# STM32.net
KiCad netlist of a schematic drawn in Altium Designer
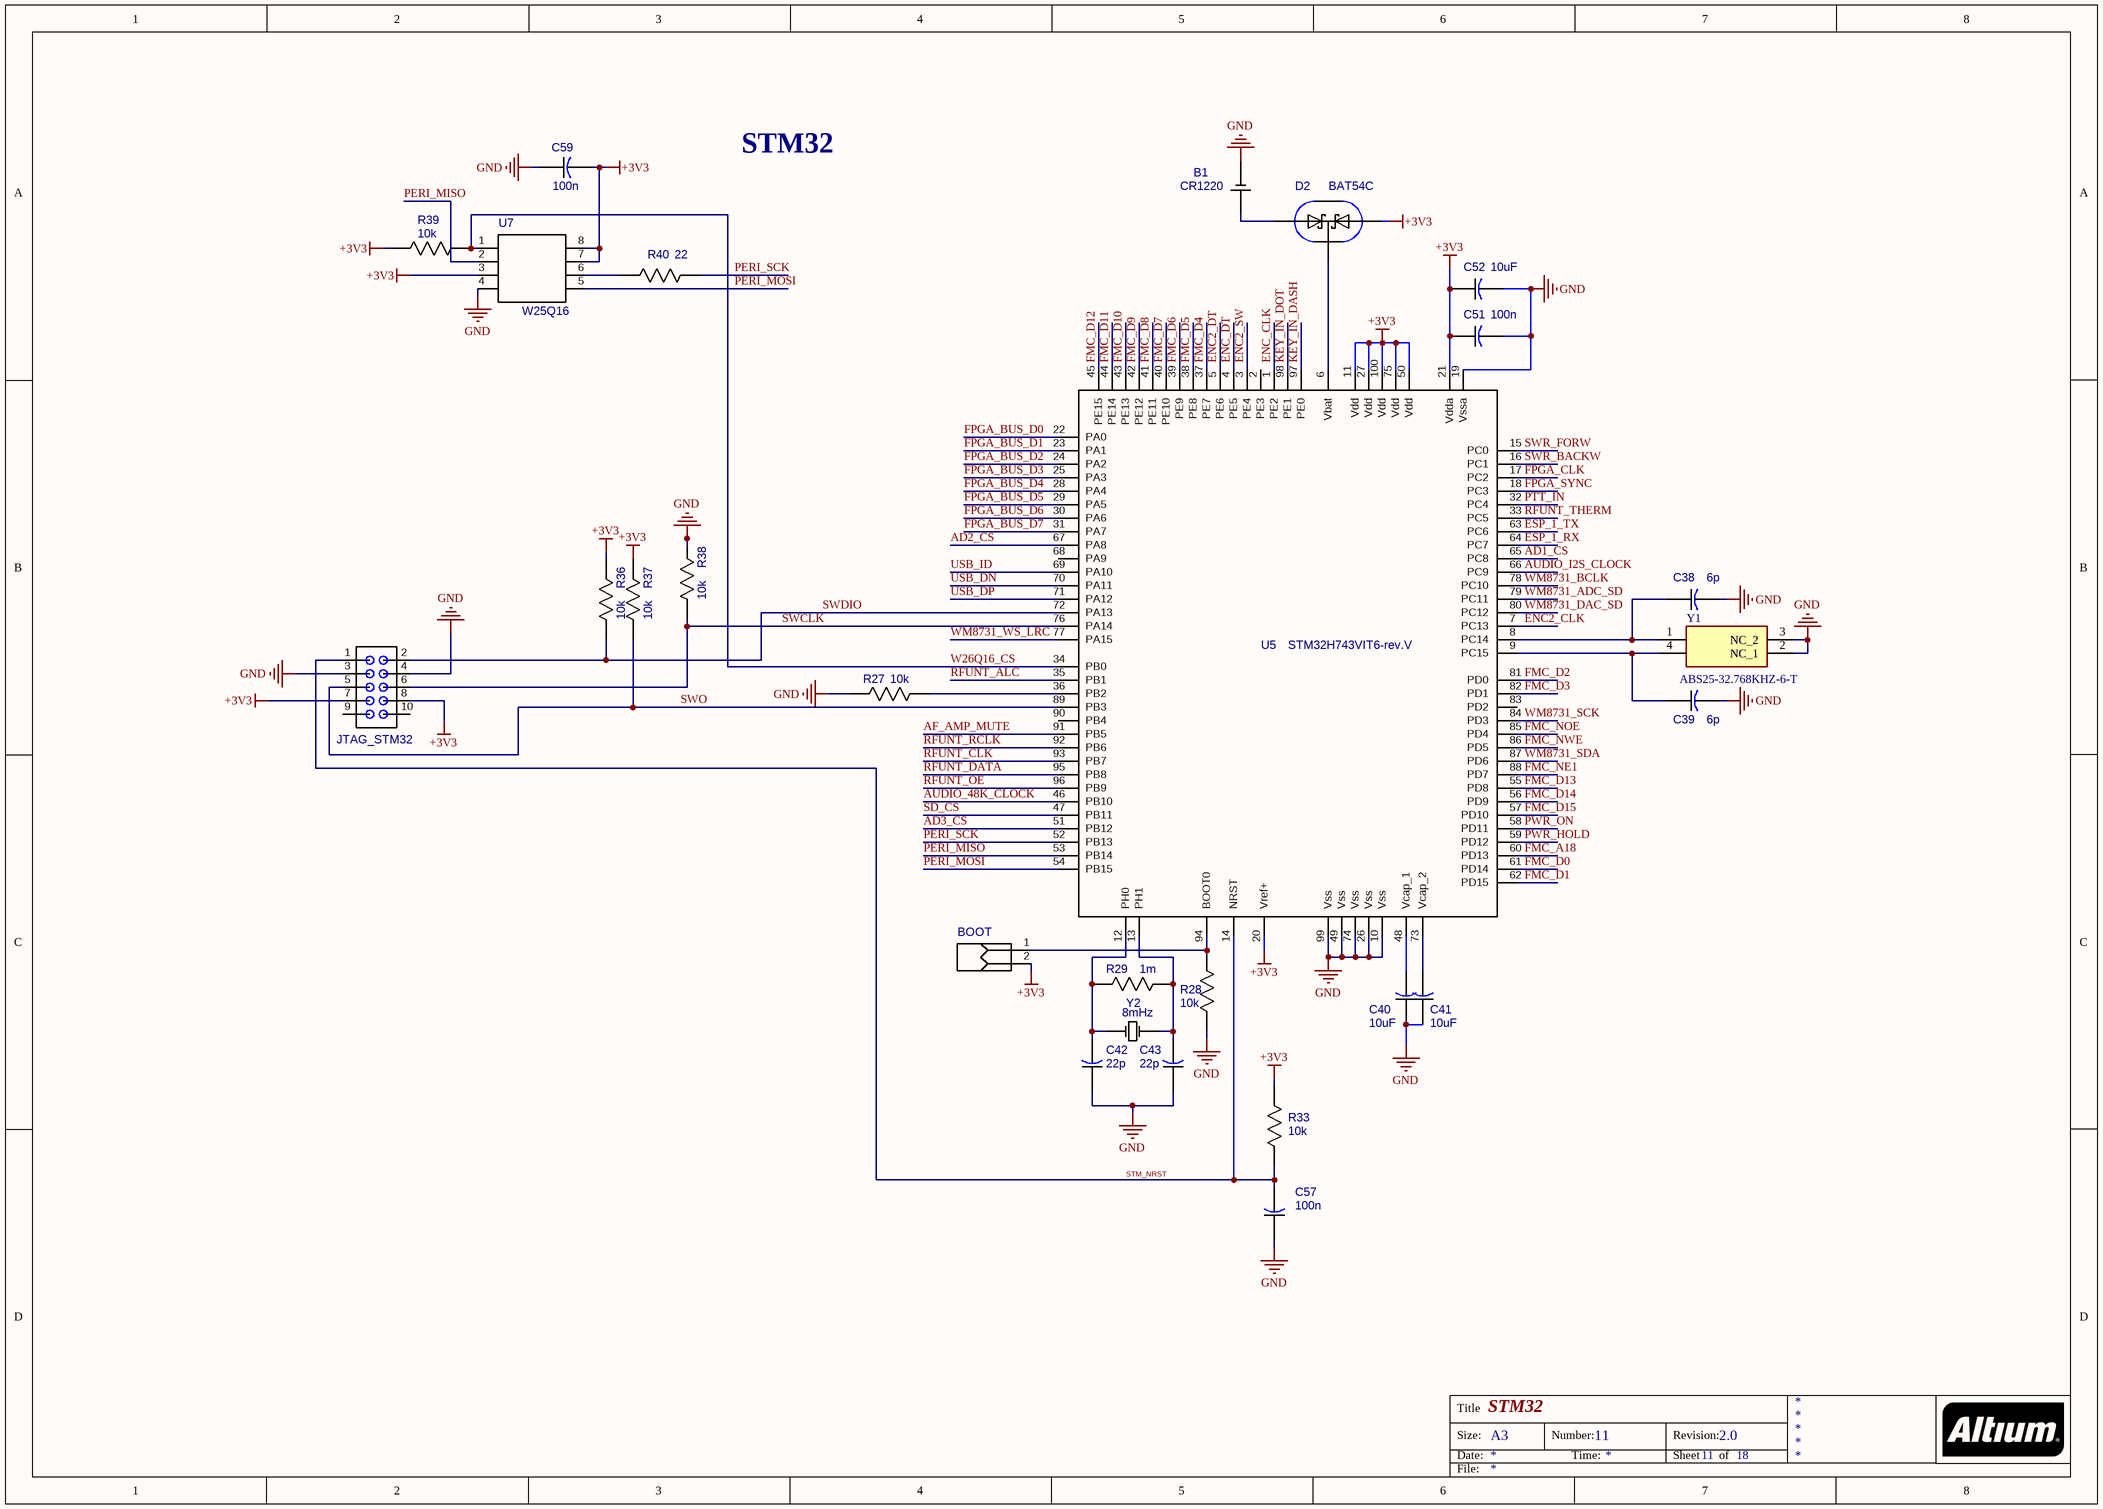
[diagram p0: STM32.SchDoc]

(export (version "E")
  (design (tool "Eeschema 10.0.6"))
  (components
    (comp (ref "B1")
      (value "CR1220")
      (footprint "KLS5-CR1220-01")
      (description "BR1632A/FA")
      (libsource (lib "*") (part "BR1632A/FA"))
    )
    (comp (ref "BOOT")
      (value "~")
      (footprint "51022-0200")
      (description "2 Pin")
      (libsource (lib "*") (part "51022-0200"))
    )
    (comp (ref "C38")
      (value "6p")
      (footprint "CAP_0805")
      (description "CAP_0805")
      (libsource (lib "*") (part "CAP_0805"))
    )
    (comp (ref "C39")
      (value "6p")
      (footprint "CAP_0805")
      (description "CAP_0805")
      (libsource (lib "*") (part "CAP_0805"))
    )
    (comp (ref "C40")
      (value "10uF")
      (footprint "CAP_0805")
      (description "CAP_0805")
      (libsource (lib "*") (part "CAP_0805"))
    )
    (comp (ref "C41")
      (value "10uF")
      (footprint "CAP_0805")
      (description "CAP_0805")
      (libsource (lib "*") (part "CAP_0805"))
    )
    (comp (ref "C42")
      (value "22p")
      (footprint "CAP_0805")
      (description "CAP_0805")
      (libsource (lib "*") (part "CAP_0805"))
    )
    (comp (ref "C43")
      (value "22p")
      (footprint "CAP_0805")
      (description "CAP_0805")
      (libsource (lib "*") (part "CAP_0805"))
    )
    (comp (ref "C51")
      (value "100n")
      (footprint "CAP_0805")
      (description "CAP_0805")
      (libsource (lib "*") (part "CAP_0805"))
    )
    (comp (ref "C52")
      (value "10uF")
      (footprint "CAP_0805")
      (description "CAP_0805")
      (libsource (lib "*") (part "CAP_0805"))
    )
    (comp (ref "C57")
      (value "100n")
      (footprint "CAP_0805")
      (description "CAP_0805")
      (libsource (lib "*") (part "CAP_0805"))
    )
    (comp (ref "C59")
      (value "100n")
      (footprint "CAP_0805")
      (description "CAP_0805")
      (libsource (lib "*") (part "CAP_0805"))
    )
    (comp (ref "D2") (value "BAT54C") (footprint "BAT54C") (libsource (lib "*") (part "BAT54C")))
    (comp (ref "JTAG_STM32")
      (value "~")
      (footprint "IDC10")
      (description "2*5 Pin")
      (libsource (lib "*") (part "IDC10"))
    )
    (comp (ref "R27")
      (value "10k")
      (footprint "RES_0805")
      (description "RES_0805")
      (libsource (lib "*") (part "RES_0805"))
    )
    (comp (ref "R28")
      (value "10k")
      (footprint "RES_0805")
      (description "RES_0805")
      (libsource (lib "*") (part "RES_0805"))
    )
    (comp (ref "R29")
      (value "1m")
      (footprint "RES_0805")
      (description "RES_0805")
      (libsource (lib "*") (part "RES_0805"))
    )
    (comp (ref "R33")
      (value "10k")
      (footprint "RES_0805")
      (description "RES_0805")
      (libsource (lib "*") (part "RES_0805"))
    )
    (comp (ref "R36")
      (value "10k")
      (footprint "RES_0805")
      (description "RES_0805")
      (libsource (lib "*") (part "RES_0805"))
    )
    (comp (ref "R37")
      (value "10k")
      (footprint "RES_0805")
      (description "RES_0805")
      (libsource (lib "*") (part "RES_0805"))
    )
    (comp (ref "R38")
      (value "10k")
      (footprint "RES_0805")
      (description "RES_0805")
      (libsource (lib "*") (part "RES_0805"))
    )
    (comp (ref "R39")
      (value "10k")
      (footprint "RES_0805")
      (description "RES_0805")
      (libsource (lib "*") (part "RES_0805"))
    )
    (comp (ref "R40")
      (value "22")
      (footprint "RES_0805")
      (description "RES_0805")
      (libsource (lib "*") (part "RES_0805"))
    )
    (comp (ref "U5")
      (value "STM32H743VIT6-rev.V")
      (footprint "STM32H743VIT6")
      (description "STM32H743VIT6")
      (libsource (lib "*") (part "STM32H743VIT6"))
    )
    (comp (ref "U7") (value "W25Q16") (footprint "W25Q16") (libsource (lib "*") (part "W25Q16")))
    (comp (ref "Y1")
      (value "ABS25-32.768KHZ-6-T")
      (footprint "SamacSys:ABS25")
      (description "Crystal or Oscillator")
      (fields
        (field (name "MOUSER PART NUMBER") "815-ABS25-32.768K6-T")
        (field (name "RS PART NUMBER") "1712795P")
      )
      (libsource (lib "*") (part "ABS25-32.768KHZ-6-T"))
    )
    (comp (ref "Y2")
      (value "8mHz")
      (footprint "ECS-200-20-1")
      (description "ECS-200-20-1")
      (libsource (lib "*") (part "ECS-200-20-1"))
    )
  )
  (nets
    (net (code "1") (name "+3V3") (class "Default")
      (node (ref "BOOT") (pin "2") (pinfunction "2_2") (pintype "passive"))
      (node (ref "C51") (pin "1") (pinfunction "1_1") (pintype "passive"))
      (node (ref "C52") (pin "1") (pinfunction "1_1") (pintype "passive"))
      (node (ref "C59") (pin "2") (pinfunction "2_2") (pintype "passive"))
      (node (ref "D2") (pin "1") (pinfunction "(A1)_1") (pintype "passive"))
      (node (ref "JTAG_STM32") (pin "7") (pinfunction "7_7") (pintype "passive"))
      (node (ref "JTAG_STM32") (pin "8") (pinfunction "8_8") (pintype "passive"))
      (node (ref "R33") (pin "2") (pinfunction "2_2") (pintype "passive"))
      (node (ref "R36") (pin "1") (pinfunction "1_1") (pintype "passive"))
      (node (ref "R37") (pin "1") (pinfunction "1_1") (pintype "passive"))
      (node (ref "R39") (pin "1") (pinfunction "1_1") (pintype "passive"))
      (node (ref "U5") (pin "100") (pinfunction "Vdd_100") (pintype "passive"))
      (node (ref "U5") (pin "11") (pinfunction "Vdd_11") (pintype "passive"))
      (node (ref "U5") (pin "20") (pinfunction "Vref+_20") (pintype "passive"))
      (node (ref "U5") (pin "21") (pinfunction "Vdda_21") (pintype "passive"))
      (node (ref "U5") (pin "27") (pinfunction "Vdd_27") (pintype "passive"))
      (node (ref "U5") (pin "50") (pinfunction "Vdd_50") (pintype "passive"))
      (node (ref "U5") (pin "75") (pinfunction "Vdd_75") (pintype "passive"))
      (node (ref "U7") (pin "3") (pinfunction "WP_3") (pintype "passive"))
      (node (ref "U7") (pin "7") (pinfunction "HOLD_7") (pintype "passive"))
      (node (ref "U7") (pin "8") (pinfunction "VCC_8") (pintype "passive"))
    )
    (net (code "2") (name "/AD1_CS") (class "Default")
      (node (ref "U5") (pin "65") (pinfunction "PC8_65") (pintype "passive"))
    )
    (net (code "3") (name "/AD2_CS") (class "Default")
      (node (ref "U5") (pin "67") (pinfunction "PA8_67") (pintype "passive"))
    )
    (net (code "4") (name "/AD3_CS") (class "Default")
      (node (ref "U5") (pin "51") (pinfunction "PB12_51") (pintype "passive"))
    )
    (net (code "5") (name "/AF_AMP_MUTE") (class "Default")
      (node (ref "U5") (pin "91") (pinfunction "PB5_91") (pintype "passive"))
    )
    (net (code "6") (name "/AUDIO_48K_CLOCK") (class "Default")
      (node (ref "U5") (pin "46") (pinfunction "PB10_46") (pintype "passive"))
    )
    (net (code "7") (name "/AUDIO_I2S_CLOCK") (class "Default")
      (node (ref "U5") (pin "66") (pinfunction "PC9_66") (pintype "passive"))
    )
    (net (code "8") (name "/ENC2_CLK") (class "Default")
      (node (ref "U5") (pin "7") (pinfunction "PC13_7") (pintype "passive"))
    )
    (net (code "9") (name "/ENC2_DT") (class "Default")
      (node (ref "U5") (pin "5") (pinfunction "PE6_5") (pintype "passive"))
    )
    (net (code "10") (name "/ENC2_SW") (class "Default")
      (node (ref "U5") (pin "3") (pinfunction "PE4_3") (pintype "passive"))
    )
    (net (code "11") (name "/ENC_CLK") (class "Default")
      (node (ref "U5") (pin "1") (pinfunction "PE2_1") (pintype "passive"))
    )
    (net (code "12") (name "/ENC_DT") (class "Default")
      (node (ref "U5") (pin "4") (pinfunction "PE5_4") (pintype "passive"))
    )
    (net (code "13") (name "/ESP_1_RX") (class "Default")
      (node (ref "U5") (pin "64") (pinfunction "PC7_64") (pintype "passive"))
    )
    (net (code "14") (name "/ESP_1_TX") (class "Default")
      (node (ref "U5") (pin "63") (pinfunction "PC6_63") (pintype "passive"))
    )
    (net (code "15") (name "/FMC_A18") (class "Default")
      (node (ref "U5") (pin "60") (pinfunction "PD13_60") (pintype "passive"))
    )
    (net (code "16") (name "/FMC_D0") (class "Default")
      (node (ref "U5") (pin "61") (pinfunction "PD14_61") (pintype "passive"))
    )
    (net (code "17") (name "/FMC_D1") (class "Default")
      (node (ref "U5") (pin "62") (pinfunction "PD15_62") (pintype "passive"))
    )
    (net (code "18") (name "/FMC_D2") (class "Default")
      (node (ref "U5") (pin "81") (pinfunction "PD0_81") (pintype "passive"))
    )
    (net (code "19") (name "/FMC_D3") (class "Default")
      (node (ref "U5") (pin "82") (pinfunction "PD1_82") (pintype "passive"))
    )
    (net (code "20") (name "/FMC_D4") (class "Default")
      (node (ref "U5") (pin "37") (pinfunction "PE7_37") (pintype "passive"))
    )
    (net (code "21") (name "/FMC_D5") (class "Default")
      (node (ref "U5") (pin "38") (pinfunction "PE8_38") (pintype "passive"))
    )
    (net (code "22") (name "/FMC_D6") (class "Default")
      (node (ref "U5") (pin "39") (pinfunction "PE9_39") (pintype "passive"))
    )
    (net (code "23") (name "/FMC_D7") (class "Default")
      (node (ref "U5") (pin "40") (pinfunction "PE10_40") (pintype "passive"))
    )
    (net (code "24") (name "/FMC_D8") (class "Default")
      (node (ref "U5") (pin "41") (pinfunction "PE11_41") (pintype "passive"))
    )
    (net (code "25") (name "/FMC_D9") (class "Default")
      (node (ref "U5") (pin "42") (pinfunction "PE12_42") (pintype "passive"))
    )
    (net (code "26") (name "/FMC_D10") (class "Default")
      (node (ref "U5") (pin "43") (pinfunction "PE13_43") (pintype "passive"))
    )
    (net (code "27") (name "/FMC_D11") (class "Default")
      (node (ref "U5") (pin "44") (pinfunction "PE14_44") (pintype "passive"))
    )
    (net (code "28") (name "/FMC_D12") (class "Default")
      (node (ref "U5") (pin "45") (pinfunction "PE15_45") (pintype "passive"))
    )
    (net (code "29") (name "/FMC_D13") (class "Default")
      (node (ref "U5") (pin "55") (pinfunction "PD8_55") (pintype "passive"))
    )
    (net (code "30") (name "/FMC_D14") (class "Default")
      (node (ref "U5") (pin "56") (pinfunction "PD9_56") (pintype "passive"))
    )
    (net (code "31") (name "/FMC_D15") (class "Default")
      (node (ref "U5") (pin "57") (pinfunction "PD10_57") (pintype "passive"))
    )
    (net (code "32") (name "/FMC_NE1") (class "Default")
      (node (ref "U5") (pin "88") (pinfunction "PD7_88") (pintype "passive"))
    )
    (net (code "33") (name "/FMC_NOE") (class "Default")
      (node (ref "U5") (pin "85") (pinfunction "PD4_85") (pintype "passive"))
    )
    (net (code "34") (name "/FMC_NWE") (class "Default")
      (node (ref "U5") (pin "86") (pinfunction "PD5_86") (pintype "passive"))
    )
    (net (code "35") (name "/FPGA_BUS_D0") (class "Default")
      (node (ref "U5") (pin "22") (pinfunction "PA0_22") (pintype "passive"))
    )
    (net (code "36") (name "/FPGA_BUS_D1") (class "Default")
      (node (ref "U5") (pin "23") (pinfunction "PA1_23") (pintype "passive"))
    )
    (net (code "37") (name "/FPGA_BUS_D2") (class "Default")
      (node (ref "U5") (pin "24") (pinfunction "PA2_24") (pintype "passive"))
    )
    (net (code "38") (name "/FPGA_BUS_D3") (class "Default")
      (node (ref "U5") (pin "25") (pinfunction "PA3_25") (pintype "passive"))
    )
    (net (code "39") (name "/FPGA_BUS_D4") (class "Default")
      (node (ref "U5") (pin "28") (pinfunction "PA4_28") (pintype "passive"))
    )
    (net (code "40") (name "/FPGA_BUS_D5") (class "Default")
      (node (ref "U5") (pin "29") (pinfunction "PA5_29") (pintype "passive"))
    )
    (net (code "41") (name "/FPGA_BUS_D6") (class "Default")
      (node (ref "U5") (pin "30") (pinfunction "PA6_30") (pintype "passive"))
    )
    (net (code "42") (name "/FPGA_BUS_D7") (class "Default")
      (node (ref "U5") (pin "31") (pinfunction "PA7_31") (pintype "passive"))
    )
    (net (code "43") (name "/FPGA_CLK") (class "Default")
      (node (ref "U5") (pin "17") (pinfunction "PC2_17") (pintype "passive"))
    )
    (net (code "44") (name "/FPGA_SYNC") (class "Default")
      (node (ref "U5") (pin "18") (pinfunction "PC3_18") (pintype "passive"))
    )
    (net (code "45") (name "/KEY_IN_DASH") (class "Default")
      (node (ref "U5") (pin "97") (pinfunction "PE0_97") (pintype "passive"))
    )
    (net (code "46") (name "/KEY_IN_DOT") (class "Default")
      (node (ref "U5") (pin "98") (pinfunction "PE1_98") (pintype "passive"))
    )
    (net (code "47") (name "/PERI_MISO") (class "Default")
      (node (ref "U5") (pin "53") (pinfunction "PB14_53") (pintype "passive"))
      (node (ref "U7") (pin "2") (pinfunction "SO_2") (pintype "passive"))
    )
    (net (code "48") (name "/PERI_MOSI") (class "Default")
      (node (ref "U5") (pin "54") (pinfunction "PB15_54") (pintype "passive"))
      (node (ref "U7") (pin "5") (pinfunction "SI_5") (pintype "passive"))
    )
    (net (code "49") (name "/PERI_SCK") (class "Default")
      (node (ref "R40") (pin "2") (pinfunction "2_2") (pintype "passive"))
      (node (ref "U5") (pin "52") (pinfunction "PB13_52") (pintype "passive"))
    )
    (net (code "50") (name "/PTT_IN") (class "Default")
      (node (ref "U5") (pin "32") (pinfunction "PC4_32") (pintype "passive"))
    )
    (net (code "51") (name "/PWR_HOLD") (class "Default")
      (node (ref "U5") (pin "59") (pinfunction "PD12_59") (pintype "passive"))
    )
    (net (code "52") (name "/PWR_ON") (class "Default")
      (node (ref "U5") (pin "58") (pinfunction "PD11_58") (pintype "passive"))
    )
    (net (code "53") (name "/RFUNT_ALC") (class "Default")
      (node (ref "U5") (pin "35") (pinfunction "PB1_35") (pintype "passive"))
    )
    (net (code "54") (name "/RFUNT_CLK") (class "Default")
      (node (ref "U5") (pin "93") (pinfunction "PB7_93") (pintype "passive"))
    )
    (net (code "55") (name "/RFUNT_DATA") (class "Default")
      (node (ref "U5") (pin "95") (pinfunction "PB8_95") (pintype "passive"))
    )
    (net (code "56") (name "/RFUNT_OE") (class "Default")
      (node (ref "U5") (pin "96") (pinfunction "PB9_96") (pintype "passive"))
    )
    (net (code "57") (name "/RFUNT_RCLK") (class "Default")
      (node (ref "U5") (pin "92") (pinfunction "PB6_92") (pintype "passive"))
    )
    (net (code "58") (name "/RFUNT_THERM") (class "Default")
      (node (ref "U5") (pin "33") (pinfunction "PC5_33") (pintype "passive"))
    )
    (net (code "59") (name "/SD_CS") (class "Default")
      (node (ref "U5") (pin "47") (pinfunction "PB11_47") (pintype "passive"))
    )
    (net (code "60") (name "/STM_NRST") (class "Default")
      (node (ref "C57") (pin "2") (pinfunction "2_2") (pintype "passive"))
      (node (ref "JTAG_STM32") (pin "1") (pinfunction "1_1") (pintype "passive"))
      (node (ref "R33") (pin "1") (pinfunction "1_1") (pintype "passive"))
      (node (ref "U5") (pin "14") (pinfunction "NRST_14") (pintype "passive"))
    )
    (net (code "61") (name "/SWCLK") (class "Default")
      (node (ref "JTAG_STM32") (pin "6") (pinfunction "6_6") (pintype "passive"))
      (node (ref "R38") (pin "2") (pinfunction "2_2") (pintype "passive"))
      (node (ref "U5") (pin "76") (pinfunction "PA14_76") (pintype "passive"))
    )
    (net (code "62") (name "/SWDIO") (class "Default")
      (node (ref "JTAG_STM32") (pin "2") (pinfunction "2_2") (pintype "passive"))
      (node (ref "R36") (pin "2") (pinfunction "2_2") (pintype "passive"))
      (node (ref "U5") (pin "72") (pinfunction "PA13_72") (pintype "passive"))
    )
    (net (code "63") (name "/SWO") (class "Default")
      (node (ref "JTAG_STM32") (pin "5") (pinfunction "5_5") (pintype "passive"))
      (node (ref "R37") (pin "2") (pinfunction "2_2") (pintype "passive"))
      (node (ref "U5") (pin "89") (pinfunction "PB3_89") (pintype "passive"))
    )
    (net (code "64") (name "/SWR_BACKW") (class "Default")
      (node (ref "U5") (pin "16") (pinfunction "PC1_16") (pintype "passive"))
    )
    (net (code "65") (name "/SWR_FORW") (class "Default")
      (node (ref "U5") (pin "15") (pinfunction "PC0_15") (pintype "passive"))
    )
    (net (code "66") (name "/USB_DN") (class "Default")
      (node (ref "U5") (pin "70") (pinfunction "PA11_70") (pintype "passive"))
    )
    (net (code "67") (name "/USB_DP") (class "Default")
      (node (ref "U5") (pin "71") (pinfunction "PA12_71") (pintype "passive"))
    )
    (net (code "68") (name "/USB_ID") (class "Default")
      (node (ref "U5") (pin "69") (pinfunction "PA10_69") (pintype "passive"))
    )
    (net (code "69") (name "/W26Q16_CS") (class "Default")
      (node (ref "R39") (pin "2") (pinfunction "2_2") (pintype "passive"))
      (node (ref "U5") (pin "34") (pinfunction "PB0_34") (pintype "passive"))
      (node (ref "U7") (pin "1") (pinfunction "CS_1") (pintype "passive"))
    )
    (net (code "70") (name "/WM8731_ADC_SD") (class "Default")
      (node (ref "U5") (pin "79") (pinfunction "PC11_79") (pintype "passive"))
    )
    (net (code "71") (name "/WM8731_BCLK") (class "Default")
      (node (ref "U5") (pin "78") (pinfunction "PC10_78") (pintype "passive"))
    )
    (net (code "72") (name "/WM8731_DAC_SD") (class "Default")
      (node (ref "U5") (pin "80") (pinfunction "PC12_80") (pintype "passive"))
    )
    (net (code "73") (name "/WM8731_SCK") (class "Default")
      (node (ref "U5") (pin "84") (pinfunction "PD3_84") (pintype "passive"))
    )
    (net (code "74") (name "/WM8731_SDA") (class "Default")
      (node (ref "U5") (pin "87") (pinfunction "PD6_87") (pintype "passive"))
    )
    (net (code "75") (name "/WM8731_WS_LRC") (class "Default")
      (node (ref "U5") (pin "77") (pinfunction "PA15_77") (pintype "passive"))
    )
    (net (code "76") (name "GND") (class "Default")
      (node (ref "B1") (pin "2") (pinfunction "NEG_2") (pintype "passive"))
      (node (ref "C38") (pin "2") (pinfunction "2_2") (pintype "passive"))
      (node (ref "C39") (pin "2") (pinfunction "2_2") (pintype "passive"))
      (node (ref "C40") (pin "1") (pinfunction "1_1") (pintype "passive"))
      (node (ref "C41") (pin "1") (pinfunction "1_1") (pintype "passive"))
      (node (ref "C42") (pin "1") (pinfunction "1_1") (pintype "passive"))
      (node (ref "C43") (pin "1") (pinfunction "1_1") (pintype "passive"))
      (node (ref "C51") (pin "2") (pinfunction "2_2") (pintype "passive"))
      (node (ref "C52") (pin "2") (pinfunction "2_2") (pintype "passive"))
      (node (ref "C57") (pin "1") (pinfunction "1_1") (pintype "passive"))
      (node (ref "C59") (pin "1") (pinfunction "1_1") (pintype "passive"))
      (node (ref "JTAG_STM32") (pin "3") (pinfunction "3_3") (pintype "passive"))
      (node (ref "JTAG_STM32") (pin "4") (pinfunction "4_4") (pintype "passive"))
      (node (ref "R27") (pin "1") (pinfunction "1_1") (pintype "passive"))
      (node (ref "R28") (pin "1") (pinfunction "1_1") (pintype "passive"))
      (node (ref "R38") (pin "1") (pinfunction "1_1") (pintype "passive"))
      (node (ref "U5") (pin "10") (pinfunction "Vss_10") (pintype "passive"))
      (node (ref "U5") (pin "19") (pinfunction "Vssa_19") (pintype "passive"))
      (node (ref "U5") (pin "26") (pinfunction "Vss_26") (pintype "passive"))
      (node (ref "U5") (pin "49") (pinfunction "Vss_49") (pintype "passive"))
      (node (ref "U5") (pin "74") (pinfunction "Vss_74") (pintype "passive"))
      (node (ref "U5") (pin "99") (pinfunction "Vss_99") (pintype "passive"))
      (node (ref "U7") (pin "4") (pinfunction "GND_4") (pintype "passive"))
      (node (ref "Y1") (pin "2") (pinfunction "NC_1_2") (pintype "passive"))
      (node (ref "Y1") (pin "3") (pinfunction "NC_2_3") (pintype "passive"))
    )
    (net (code "77") (name "Net-(B1-POS)") (class "Default")
      (node (ref "B1") (pin "1") (pinfunction "POS_1") (pintype "passive"))
      (node (ref "D2") (pin "2") (pinfunction "(A2)_2") (pintype "passive"))
    )
    (net (code "78") (name "Net-(D2-(K1),(K2))") (class "Default")
      (node (ref "D2") (pin "3") (pinfunction "(K1),(K2)_3") (pintype "passive"))
      (node (ref "U5") (pin "6") (pinfunction "Vbat_6") (pintype "passive"))
    )
    (net (code "79") (name "Net-(U5-BOOT0)") (class "Default")
      (node (ref "BOOT") (pin "1") (pinfunction "1_1") (pintype "passive"))
      (node (ref "R28") (pin "2") (pinfunction "2_2") (pintype "passive"))
      (node (ref "U5") (pin "94") (pinfunction "BOOT0_94") (pintype "passive"))
    )
    (net (code "80") (name "Net-(U5-PB2)") (class "Default")
      (node (ref "R27") (pin "2") (pinfunction "2_2") (pintype "passive"))
      (node (ref "U5") (pin "36") (pinfunction "PB2_36") (pintype "passive"))
    )
    (net (code "81") (name "Net-(U5-PC14)") (class "Default")
      (node (ref "C38") (pin "1") (pinfunction "1_1") (pintype "passive"))
      (node (ref "U5") (pin "8") (pinfunction "PC14_8") (pintype "passive"))
      (node (ref "Y1") (pin "1") (pinfunction "1_1") (pintype "passive"))
    )
    (net (code "82") (name "Net-(U5-PC15)") (class "Default")
      (node (ref "C39") (pin "1") (pinfunction "1_1") (pintype "passive"))
      (node (ref "U5") (pin "9") (pinfunction "PC15_9") (pintype "passive"))
      (node (ref "Y1") (pin "4") (pinfunction "4_4") (pintype "passive"))
    )
    (net (code "83") (name "Net-(U5-PH0)") (class "Default")
      (node (ref "C42") (pin "2") (pinfunction "2_2") (pintype "passive"))
      (node (ref "R29") (pin "1") (pinfunction "1_1") (pintype "passive"))
      (node (ref "U5") (pin "12") (pinfunction "PH0_12") (pintype "passive"))
      (node (ref "Y2") (pin "1") (pinfunction "OSC1_1") (pintype "passive"))
    )
    (net (code "84") (name "Net-(U5-PH1)") (class "Default")
      (node (ref "C43") (pin "2") (pinfunction "2_2") (pintype "passive"))
      (node (ref "R29") (pin "2") (pinfunction "2_2") (pintype "passive"))
      (node (ref "U5") (pin "13") (pinfunction "PH1_13") (pintype "passive"))
      (node (ref "Y2") (pin "2") (pinfunction "OSC2_2") (pintype "passive"))
    )
    (net (code "85") (name "Net-(U5-Vcap_1)") (class "Default")
      (node (ref "C40") (pin "2") (pinfunction "2_2") (pintype "passive"))
      (node (ref "U5") (pin "48") (pinfunction "Vcap_1_48") (pintype "passive"))
    )
    (net (code "86") (name "Net-(U5-Vcap_2)") (class "Default")
      (node (ref "C41") (pin "2") (pinfunction "2_2") (pintype "passive"))
      (node (ref "U5") (pin "73") (pinfunction "Vcap_2_73") (pintype "passive"))
    )
    (net (code "87") (name "Net-(U7-CLK)") (class "Default")
      (node (ref "R40") (pin "1") (pinfunction "1_1") (pintype "passive"))
      (node (ref "U7") (pin "6") (pinfunction "CLK_6") (pintype "passive"))
    )
    (net (code "88") (name "unconnected-(JTAG_STM32-Pad9)") (class "Default")
      (node (ref "JTAG_STM32") (pin "9") (pinfunction "9_9") (pintype "passive"))
    )
    (net (code "89") (name "unconnected-(JTAG_STM32-Pad10)") (class "Default")
      (node (ref "JTAG_STM32") (pin "10") (pinfunction "10_10") (pintype "passive"))
    )
    (net (code "90") (name "unconnected-(U5-PA9-Pad68)") (class "Default")
      (node (ref "U5") (pin "68") (pinfunction "PA9_68") (pintype "passive"))
    )
    (net (code "91") (name "unconnected-(U5-PB4-Pad90)") (class "Default")
      (node (ref "U5") (pin "90") (pinfunction "PB4_90") (pintype "passive"))
    )
    (net (code "92") (name "unconnected-(U5-PD2-Pad83)") (class "Default")
      (node (ref "U5") (pin "83") (pinfunction "PD2_83") (pintype "passive"))
    )
    (net (code "93") (name "unconnected-(U5-PE3-Pad2)") (class "Default")
      (node (ref "U5") (pin "2") (pinfunction "PE3_2") (pintype "passive"))
    )
  )
)
